# INTERFACE.net
KiCad netlist of a schematic drawn in Altium Designer
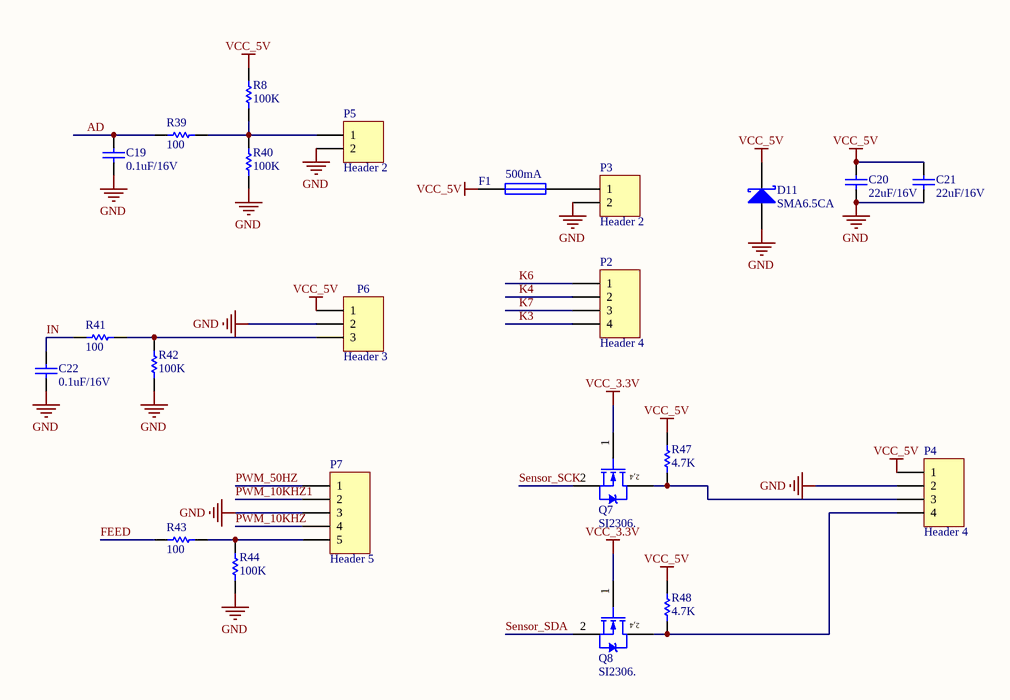
[diagram p0: INTERFACE.SchDoc]

(export (version "E")
  (design (tool "Eeschema 10.0.6"))
  (components
    (comp (ref "C19")
      (value "0.1uF/16V")
      (footprint "0603C")
      (description "Capacitor")
      (fields (field (name "PUBLISHER") "Altium Limited"))
      (libsource (lib "Miscellaneous Devices") (part "Cap"))
    )
    (comp (ref "C20")
      (value "22uF/16V")
      (footprint "0805C")
      (description "Capacitor")
      (fields (field (name "PUBLISHER") "Altium Limited"))
      (libsource (lib "Miscellaneous Devices") (part "Cap"))
    )
    (comp (ref "C21")
      (value "22uF/16V")
      (footprint "0805C")
      (description "Capacitor")
      (fields (field (name "PUBLISHER") "Altium Limited"))
      (libsource (lib "Miscellaneous Devices") (part "Cap"))
    )
    (comp (ref "C22")
      (value "0.1uF/16V")
      (footprint "0603C")
      (description "Capacitor")
      (fields (field (name "PUBLISHER") "Altium Limited"))
      (libsource (lib "Miscellaneous Devices") (part "Cap"))
    )
    (comp (ref "D11")
      (value "SMA6.5CA")
      (footprint "SMA")
      (description "Schottky Diode")
      (fields (field (name "PUBLISHER") "Altium Limited"))
      (libsource (lib "Miscellaneous Devices") (part "D Schottky"))
    )
    (comp (ref "F1")
      (value "500mA")
      (footprint "0805R")
      (description "Fuse")
      (fields (field (name "PUBLISHER") "Altium Limited"))
      (libsource (lib "Miscellaneous Devices") (part "Fuse 1"))
    )
    (comp (ref "P2")
      (value "Header 4")
      (footprint "4-2.5MM-W")
      (description "Header, 4-Pin")
      (fields (field (name "PUBLISHER") "Altium Limited"))
      (libsource (lib "Miscellaneous Connectors") (part "Header 4"))
    )
    (comp (ref "P3")
      (value "Header 2")
      (footprint "2-2.5MM-W")
      (description "Header, 2-Pin")
      (fields (field (name "PUBLISHER") "Altium Limited"))
      (libsource (lib "Miscellaneous Connectors") (part "Header 2"))
    )
    (comp (ref "P4")
      (value "Header 4")
      (footprint "4-2.5MM-W")
      (description "Header, 4-Pin")
      (fields (field (name "PUBLISHER") "Altium Limited"))
      (libsource (lib "Miscellaneous Connectors") (part "Header 4"))
    )
    (comp (ref "P5")
      (value "Header 2")
      (footprint "2-2.5MM-W")
      (description "Header, 2-Pin")
      (fields (field (name "PUBLISHER") "Altium Limited"))
      (libsource (lib "Miscellaneous Connectors") (part "Header 2"))
    )
    (comp (ref "P6")
      (value "Header 3")
      (footprint "3-2.5MM-W")
      (description "Header, 3-Pin")
      (fields (field (name "PUBLISHER") "Altium Limited"))
      (libsource (lib "Miscellaneous Connectors") (part "Header 3"))
    )
    (comp (ref "P7")
      (value "Header 5")
      (footprint "5-2.5MM-W")
      (description "Header, 5-Pin")
      (fields (field (name "PUBLISHER") "Altium Limited"))
      (libsource (lib "Miscellaneous Connectors") (part "Header 5"))
    )
    (comp (ref "Q7")
      (value "SI2306.")
      (footprint "SOT23-3")
      (description "BUK92150-55A")
      (fields (field (name "PUBLISHER") "Altium Limited"))
      (libsource (lib "Schlib1") (part "BUK92150-55A"))
    )
    (comp (ref "Q8")
      (value "SI2306.")
      (footprint "SOT23-3")
      (description "BUK92150-55A")
      (fields (field (name "PUBLISHER") "Altium Limited"))
      (libsource (lib "Schlib1") (part "BUK92150-55A"))
    )
    (comp (ref "R8")
      (value "100K")
      (footprint "0603R")
      (description "Resistor")
      (fields (field (name "PUBLISHER") "Altium Limited"))
      (libsource (lib "Miscellaneous Devices") (part "Res1"))
    )
    (comp (ref "R39")
      (value "100")
      (footprint "0603R")
      (description "Resistor")
      (fields (field (name "PUBLISHER") "Altium Limited"))
      (libsource (lib "Miscellaneous Devices") (part "Res1"))
    )
    (comp (ref "R40")
      (value "100K")
      (footprint "0603R")
      (description "Resistor")
      (fields (field (name "PUBLISHER") "Altium Limited"))
      (libsource (lib "Miscellaneous Devices") (part "Res1"))
    )
    (comp (ref "R41")
      (value "100")
      (footprint "0603R")
      (description "Resistor")
      (fields (field (name "PUBLISHER") "Altium Limited"))
      (libsource (lib "Miscellaneous Devices") (part "Res1"))
    )
    (comp (ref "R42")
      (value "100K")
      (footprint "0603R")
      (description "Resistor")
      (fields (field (name "PUBLISHER") "Altium Limited"))
      (libsource (lib "Miscellaneous Devices") (part "Res1"))
    )
    (comp (ref "R43")
      (value "100")
      (footprint "0603R")
      (description "Resistor")
      (fields (field (name "PUBLISHER") "Altium Limited"))
      (libsource (lib "Miscellaneous Devices") (part "Res1"))
    )
    (comp (ref "R44")
      (value "100K")
      (footprint "0603R")
      (description "Resistor")
      (fields (field (name "PUBLISHER") "Altium Limited"))
      (libsource (lib "Miscellaneous Devices") (part "Res1"))
    )
    (comp (ref "R47")
      (value "4.7K")
      (footprint "0603R")
      (description "Resistor")
      (fields (field (name "PUBLISHER") "Altium Limited"))
      (libsource (lib "Miscellaneous Devices") (part "Res1"))
    )
    (comp (ref "R48")
      (value "4.7K")
      (footprint "0603R")
      (description "Resistor")
      (fields (field (name "PUBLISHER") "Altium Limited"))
      (libsource (lib "Miscellaneous Devices") (part "Res1"))
    )
  )
  (nets
    (net (code "1") (name "/AD") (class "Default")
      (node (ref "C19") (pin "1") (pinfunction "1_1") (pintype "passive"))
      (node (ref "R39") (pin "1") (pinfunction "1_1") (pintype "passive"))
    )
    (net (code "2") (name "/FEED") (class "Default")
      (node (ref "R43") (pin "1") (pinfunction "1_1") (pintype "passive"))
    )
    (net (code "3") (name "/IN") (class "Default")
      (node (ref "C22") (pin "1") (pinfunction "1_1") (pintype "passive"))
      (node (ref "R41") (pin "1") (pinfunction "1_1") (pintype "passive"))
    )
    (net (code "4") (name "/K3") (class "Default")
      (node (ref "P2") (pin "4") (pinfunction "4_4") (pintype "passive"))
    )
    (net (code "5") (name "/K4") (class "Default")
      (node (ref "P2") (pin "2") (pinfunction "2_2") (pintype "passive"))
    )
    (net (code "6") (name "/K6") (class "Default")
      (node (ref "P2") (pin "1") (pinfunction "1_1") (pintype "passive"))
    )
    (net (code "7") (name "/K7") (class "Default")
      (node (ref "P2") (pin "3") (pinfunction "3_3") (pintype "passive"))
    )
    (net (code "8") (name "/PWM_10KHZ") (class "Default")
      (node (ref "P7") (pin "4") (pinfunction "4_4") (pintype "passive"))
    )
    (net (code "9") (name "/PWM_10KHZ1") (class "Default")
      (node (ref "P7") (pin "2") (pinfunction "2_2") (pintype "passive"))
    )
    (net (code "10") (name "/PWM_50HZ") (class "Default")
      (node (ref "P7") (pin "1") (pinfunction "1_1") (pintype "passive"))
    )
    (net (code "11") (name "/Sensor_SCK") (class "Default")
      (node (ref "Q7") (pin "2") (pinfunction "S_2") (pintype "passive"))
    )
    (net (code "12") (name "/Sensor_SDA") (class "Default")
      (node (ref "Q8") (pin "2") (pinfunction "S_2") (pintype "passive"))
    )
    (net (code "13") (name "GND") (class "Default")
      (node (ref "C19") (pin "2") (pinfunction "2_2") (pintype "passive"))
      (node (ref "C20") (pin "2") (pinfunction "2_2") (pintype "passive"))
      (node (ref "C21") (pin "2") (pinfunction "2_2") (pintype "passive"))
      (node (ref "C22") (pin "2") (pinfunction "2_2") (pintype "passive"))
      (node (ref "D11") (pin "1") (pinfunction "A_1") (pintype "passive"))
      (node (ref "P3") (pin "2") (pinfunction "2_2") (pintype "passive"))
      (node (ref "P4") (pin "2") (pinfunction "2_2") (pintype "passive"))
      (node (ref "P5") (pin "2") (pinfunction "2_2") (pintype "passive"))
      (node (ref "P6") (pin "2") (pinfunction "2_2") (pintype "passive"))
      (node (ref "P7") (pin "3") (pinfunction "3_3") (pintype "passive"))
      (node (ref "R40") (pin "2") (pinfunction "2_2") (pintype "passive"))
      (node (ref "R42") (pin "2") (pinfunction "2_2") (pintype "passive"))
      (node (ref "R44") (pin "2") (pinfunction "2_2") (pintype "passive"))
    )
    (net (code "14") (name "Net-(F1-Pad2)") (class "Default")
      (node (ref "F1") (pin "2") (pinfunction "2_2") (pintype "passive"))
      (node (ref "P3") (pin "1") (pinfunction "1_1") (pintype "passive"))
    )
    (net (code "15") (name "Net-(P5-Pad1)") (class "Default")
      (node (ref "P5") (pin "1") (pinfunction "1_1") (pintype "passive"))
      (node (ref "R39") (pin "2") (pinfunction "2_2") (pintype "passive"))
      (node (ref "R40") (pin "1") (pinfunction "1_1") (pintype "passive"))
      (node (ref "R8") (pin "2") (pinfunction "2_2") (pintype "passive"))
    )
    (net (code "16") (name "Net-(P6-Pad3)") (class "Default")
      (node (ref "P6") (pin "3") (pinfunction "3_3") (pintype "passive"))
      (node (ref "R41") (pin "2") (pinfunction "2_2") (pintype "passive"))
      (node (ref "R42") (pin "1") (pinfunction "1_1") (pintype "passive"))
    )
    (net (code "17") (name "Net-(P7-Pad5)") (class "Default")
      (node (ref "P7") (pin "5") (pinfunction "5_5") (pintype "passive"))
      (node (ref "R43") (pin "2") (pinfunction "2_2") (pintype "passive"))
      (node (ref "R44") (pin "1") (pinfunction "1_1") (pintype "passive"))
    )
    (net (code "18") (name "Net-(Q7-D)") (class "Default")
      (node (ref "P4") (pin "3") (pinfunction "3_3") (pintype "passive"))
      (node (ref "Q7") (pin "3") (pinfunction "D_3") (pintype "passive"))
      (node (ref "R47") (pin "1") (pinfunction "1_1") (pintype "passive"))
    )
    (net (code "19") (name "Net-(Q8-D)") (class "Default")
      (node (ref "P4") (pin "4") (pinfunction "4_4") (pintype "passive"))
      (node (ref "Q8") (pin "3") (pinfunction "D_3") (pintype "passive"))
      (node (ref "R48") (pin "1") (pinfunction "1_1") (pintype "passive"))
    )
    (net (code "20") (name "VCC_3.3V") (class "Default")
      (node (ref "Q7") (pin "1") (pinfunction "G_1") (pintype "passive"))
      (node (ref "Q8") (pin "1") (pinfunction "G_1") (pintype "passive"))
    )
    (net (code "21") (name "VCC_5V") (class "Default")
      (node (ref "C20") (pin "1") (pinfunction "1_1") (pintype "passive"))
      (node (ref "C21") (pin "1") (pinfunction "1_1") (pintype "passive"))
      (node (ref "D11") (pin "2") (pinfunction "K_2") (pintype "passive"))
      (node (ref "F1") (pin "1") (pinfunction "1_1") (pintype "passive"))
      (node (ref "P4") (pin "1") (pinfunction "1_1") (pintype "passive"))
      (node (ref "P6") (pin "1") (pinfunction "1_1") (pintype "passive"))
      (node (ref "R47") (pin "2") (pinfunction "2_2") (pintype "passive"))
      (node (ref "R48") (pin "2") (pinfunction "2_2") (pintype "passive"))
      (node (ref "R8") (pin "1") (pinfunction "1_1") (pintype "passive"))
    )
  )
)
